# LOGGING.net
KiCad netlist of a schematic drawn in Altium Designer
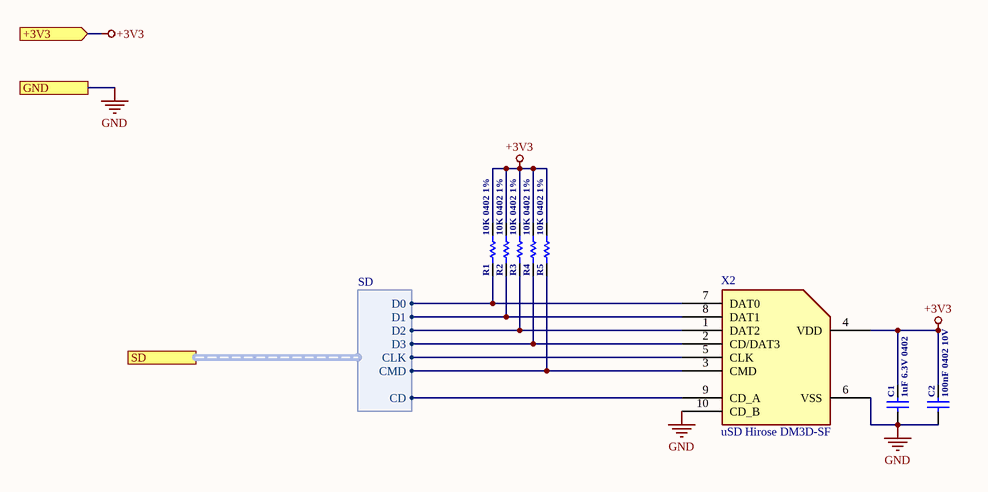
[diagram p0: LOGGING.SchDoc]

(export (version "E")
  (design (tool "Eeschema 10.0.6"))
  (components
    (comp (ref "C1")
      (value "1uF 6.3V 0402")
      (fields
        (field (name "MANUFACTURER") "Samsung")
        (field (name "MANUFACTURER PART NUMBER") "CL05A105KQ5NNNC")
      )
      (libsource (lib "CondensadoresGenericos") (part "CL05A105KQ5NNNC 1uF 0402"))
    )
    (comp (ref "C2")
      (value "100nF 0402 10V")
      (description "Cap Ceramic 0.1uF 10V X5R 10% SMD 0402 85C Paper T/R")
      (fields
        (field (name "MANUFACTURER") "Samsung")
        (field (name "MANUFACTURER PART NUMBER") "CL05A104KP5NNNC")
      )
      (libsource (lib "CondensadoresGenericos") (part "CL05A104KP5NNNC 100nF 0402 10V"))
    )
    (comp (ref "R1")
      (value "10K 0402 1%")
      (footprint "Resistor_0402")
      (description "RES SMD 10K OHM 1% 1/16W 0402")
      (fields
        (field (name "MANUFACTURER") "Yageo")
        (field (name "MANUFACTURER PART NUMBER") "AC0402FR-0710KL")
      )
      (libsource (lib "ResistenciasGenericas") (part "AC0402FR-0710KL 10K 0402 1%"))
    )
    (comp (ref "R2")
      (value "10K 0402 1%")
      (footprint "Resistor_0402")
      (description "RES SMD 10K OHM 1% 1/16W 0402")
      (fields
        (field (name "MANUFACTURER") "Yageo")
        (field (name "MANUFACTURER PART NUMBER") "AC0402FR-0710KL")
      )
      (libsource (lib "ResistenciasGenericas") (part "AC0402FR-0710KL 10K 0402 1%"))
    )
    (comp (ref "R3")
      (value "10K 0402 1%")
      (footprint "Resistor_0402")
      (description "RES SMD 10K OHM 1% 1/16W 0402")
      (fields
        (field (name "MANUFACTURER") "Yageo")
        (field (name "MANUFACTURER PART NUMBER") "AC0402FR-0710KL")
      )
      (libsource (lib "ResistenciasGenericas") (part "AC0402FR-0710KL 10K 0402 1%"))
    )
    (comp (ref "R4")
      (value "10K 0402 1%")
      (footprint "Resistor_0402")
      (description "RES SMD 10K OHM 1% 1/16W 0402")
      (fields
        (field (name "MANUFACTURER") "Yageo")
        (field (name "MANUFACTURER PART NUMBER") "AC0402FR-0710KL")
      )
      (libsource (lib "ResistenciasGenericas") (part "AC0402FR-0710KL 10K 0402 1%"))
    )
    (comp (ref "R5")
      (value "10K 0402 1%")
      (footprint "Resistor_0402")
      (description "RES SMD 10K OHM 1% 1/16W 0402")
      (fields
        (field (name "MANUFACTURER") "Yageo")
        (field (name "MANUFACTURER PART NUMBER") "AC0402FR-0710KL")
      )
      (libsource (lib "ResistenciasGenericas") (part "AC0402FR-0710KL 10K 0402 1%"))
    )
    (comp (ref "X2")
      (value "uSD Hirose DM3D-SF")
      (fields (field (name "MANUFACTURER") "Hirose") (field (name "MANUFACTURER PART NUMBER") "DM3D-SF"))
      (libsource (lib "Miscellaneus") (part "DM3D-SF"))
    )
  )
  (nets
    (net (code "2") (name "+3V3") (class "Default")
      (node (ref "C1") (pin "2") (pinfunction "2_2") (pintype "passive"))
      (node (ref "C2") (pin "2") (pinfunction "2_2") (pintype "passive"))
      (node (ref "R1") (pin "2") (pinfunction "2_2") (pintype "passive"))
      (node (ref "R2") (pin "2") (pinfunction "2_2") (pintype "passive"))
      (node (ref "R3") (pin "2") (pinfunction "2_2") (pintype "passive"))
      (node (ref "R4") (pin "2") (pinfunction "2_2") (pintype "passive"))
      (node (ref "R5") (pin "2") (pinfunction "2_2") (pintype "passive"))
      (node (ref "X2") (pin "4") (pinfunction "VDD_4") (pintype "power_in"))
    )
    (net (code "3") (name "/CD") (class "Default")
      (node (ref "X2") (pin "9") (pinfunction "CD_A_9") (pintype "power_in"))
    )
    (net (code "4") (name "/CLK") (class "Default")
      (node (ref "X2") (pin "5") (pinfunction "CLK_5") (pintype "power_in"))
    )
    (net (code "5") (name "/CMD") (class "Default")
      (node (ref "R5") (pin "1") (pinfunction "1_1") (pintype "passive"))
      (node (ref "X2") (pin "3") (pinfunction "CMD_3") (pintype "power_in"))
    )
    (net (code "6") (name "/D0") (class "Default")
      (node (ref "R1") (pin "1") (pinfunction "1_1") (pintype "passive"))
      (node (ref "X2") (pin "7") (pinfunction "DAT0_7") (pintype "power_in"))
    )
    (net (code "7") (name "/D1") (class "Default")
      (node (ref "R2") (pin "1") (pinfunction "1_1") (pintype "passive"))
      (node (ref "X2") (pin "8") (pinfunction "DAT1_8") (pintype "power_in"))
    )
    (net (code "8") (name "/D2") (class "Default")
      (node (ref "R3") (pin "1") (pinfunction "1_1") (pintype "passive"))
      (node (ref "X2") (pin "1") (pinfunction "DAT2_1") (pintype "power_in"))
    )
    (net (code "9") (name "/D3") (class "Default")
      (node (ref "R4") (pin "1") (pinfunction "1_1") (pintype "passive"))
      (node (ref "X2") (pin "2") (pinfunction "CD/DAT3_2") (pintype "power_in"))
    )
    (net (code "11") (name "GND") (class "Default")
      (node (ref "C1") (pin "1") (pinfunction "1_1") (pintype "passive"))
      (node (ref "C2") (pin "1") (pinfunction "1_1") (pintype "passive"))
      (node (ref "X2") (pin "10") (pinfunction "CD_B_10") (pintype "power_in"))
      (node (ref "X2") (pin "6") (pinfunction "VSS_6") (pintype "power_in"))
    )
  )
)
